# Battery_and_Power.net
KiCad netlist of a schematic drawn in Altium Designer
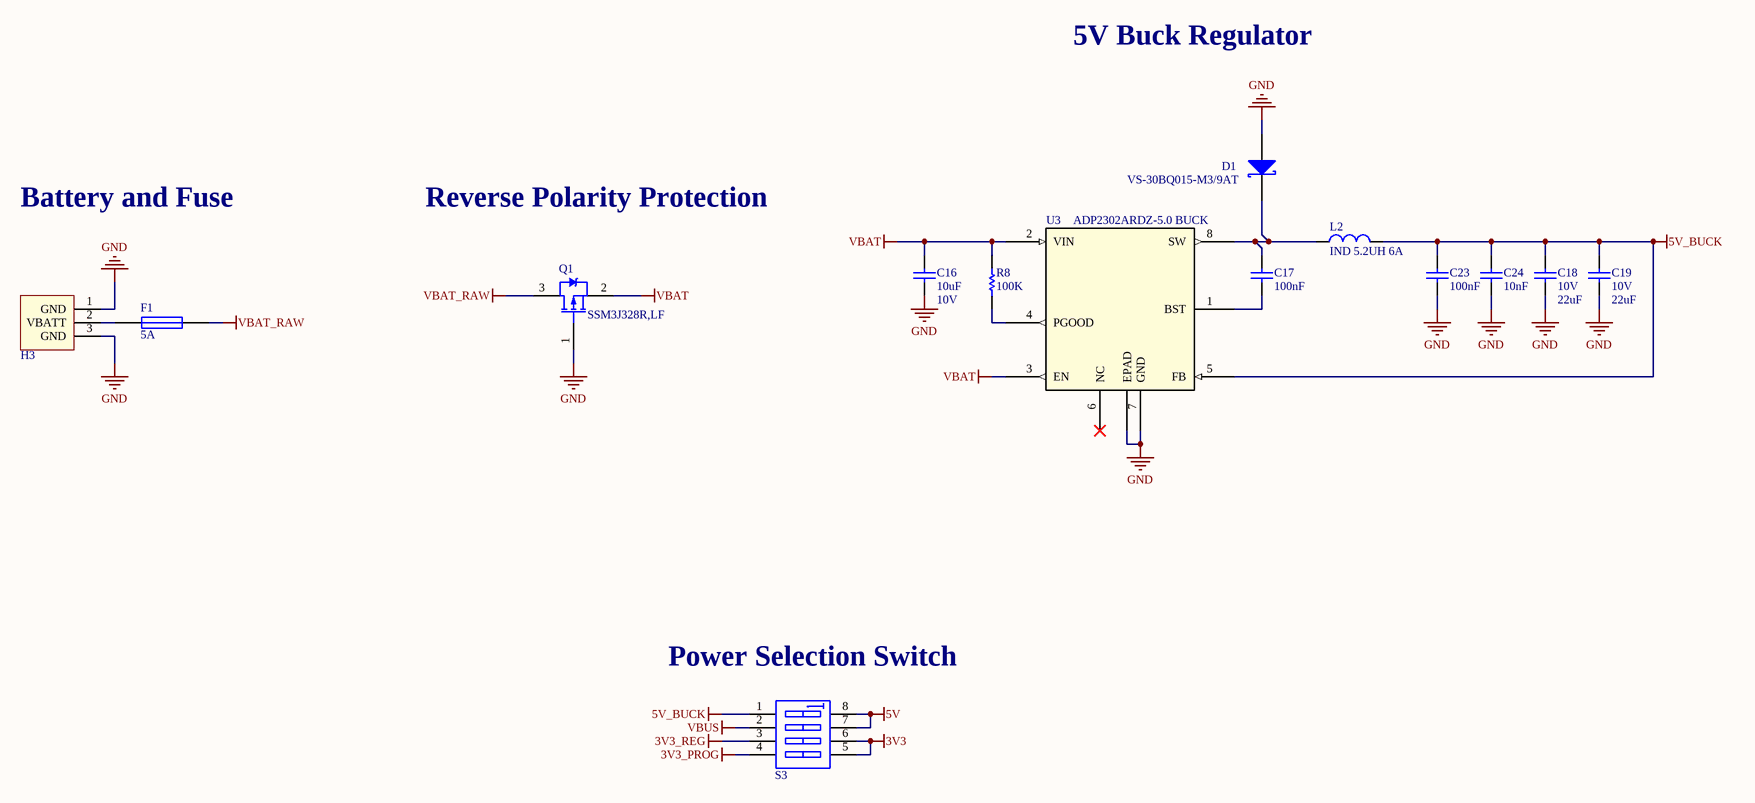
[diagram p0: Battery and Power.SchDoc]

(export (version "E")
  (design (tool "Eeschema 10.0.6"))
  (components
    (comp (ref "C16")
      (value "10uF")
      (footprint "CAPC2012L")
      (description "CAP CER 10uF X7R +-20% 10V 0805")
      (fields (field (name "MAX VOLTAGE") "10V"))
      (libsource (lib "ECE AD19Components_19V1") (part "CC_10uF_0805_10V"))
    )
    (comp (ref "C17")
      (value "100nF")
      (footprint "CAPC1608L")
      (description "CAP CER 100nF X7R +-10% 50V 0603")
      (libsource (lib "ECE AD19Components_19V1") (part "CC_100nF_0603"))
    )
    (comp (ref "C18")
      (value "22uF")
      (footprint "CAPC3216L")
      (description "CAP CER 22uF Y5V -20% +80% 10V 1206")
      (fields (field (name "MAX VOLTAGE") "10V"))
      (libsource (lib "ECE AD19Components_19V1") (part "CC_22uF_1206"))
    )
    (comp (ref "C19")
      (value "22uF")
      (footprint "CAPC3216L")
      (description "CAP CER 22uF Y5V -20% +80% 10V 1206")
      (fields (field (name "MAX VOLTAGE") "10V"))
      (libsource (lib "ECE AD19Components_19V1") (part "CC_22uF_1206"))
    )
    (comp (ref "C23")
      (value "100nF")
      (footprint "CAPC1608L")
      (description "CAP CER 100nF X7R +-10% 50V 0603")
      (libsource (lib "ECE AD19Components_19V1") (part "CC_100nF_0603"))
    )
    (comp (ref "C24")
      (value "10nF")
      (footprint "CAPC1608L")
      (description "CAP CER 10nF X7R +-10% 50V 0603")
      (libsource (lib "ECE AD19Components_19V1") (part "CC_10nF_0603"))
    )
    (comp (ref "D1")
      (value "VS-30BQ015-M3/9AT")
      (footprint "SMC")
      (description "DIODE, SCHOTTKY, 3A, 15V, DO-214AB / SMC")
      (fields (field (name "MANUFACTURER") "Vishay Semiconductors"))
      (libsource (lib "ECE AD19Components_19V1") (part "DS_VS-30BQ015-M3"))
    )
    (comp (ref "F1")
      (value "5A")
      (footprint "RESC3216N")
      (description "Fuse 5.0A Fast Acting 1206 SMD")
      (fields (field (name "MANUFACTURER PART NUMBER") "C1F5") (field (name "MANUFACTURER") "Bel TRP"))
      (libsource (lib "ECE AD19Components_19V1") (part "FS_Fuse_5.0A"))
    )
    (comp (ref "H3")
      (value "Battery_HEADER_3pin")
      (footprint "BATT_HEADER_3POS")
      (description "3Pin Header 2.54mm spacing")
      (libsource (lib "ENCE461AD19_19V2") (part "Battery_HEADER_3pin"))
    )
    (comp (ref "L2")
      (value "IND 5.2UH 6A")
      (footprint "INDUCTOR5u2")
      (description "FIXED IND 5.2UH 6A 22 MOHM SMD")
      (fields
        (field (name "MANUFACTURER") "Sumida America Components Inc.")
        (field (name "MANUFACTURER PART NUMBER") "CDRH104RNP-5R2NC")
      )
      (libsource (lib "ENCE461AD19_19V2") (part "CDRH104RNP-5R2NC"))
    )
    (comp (ref "Q1")
      (value "SSM3J328R,LF")
      (footprint "SOT23_L")
      (description "MOSFET P-CH 20V 6A SOT23-3")
      (fields
        (field (name "MANUFACTURER") "Toshiba")
        (field (name "MANUFACTURER PART NUMBER") "SSM3J328R,LF")
      )
      (libsource (lib "ECE AD19Components_19V1") (part "TM_SSM3J328R"))
    )
    (comp (ref "R8")
      (value "100K")
      (footprint "RESC1608L")
      (description "RES 100K OHM 1/10W 5% 0603 SMD")
      (libsource (lib "ECE AD19Components_19V1") (part "RS_100K"))
    )
    (comp (ref "S3")
      (value "WS_SW DIP-4")
      (footprint "DIP_SW_4WAY_SMD -")
      (description "DIP Switch, 4 Position, SPST SMD")
      (fields
        (field (name "MANUFACTURER") "OMRON ELECTRONIC COMPONENTS")
        (field (name "MANUFACTURER PART NUMBER") "A6SN-4101")
      )
      (libsource (lib "ECE AD19Components_19V1") (part "WS_SW DIP-4"))
    )
    (comp (ref "U3")
      (value "ADP2302ARDZ-5.0 BUCK")
      (footprint "RD_8_1")
      (description "IC REG BUCK 5V 2A 8SOIC")
      (fields (field (name "MANUFACTURER_PART_NUMBER") "ADP2302ARDZ-5.0-R7"))
      (libsource (lib "ENCE461AD19_19V2") (part "ADP2302ARDZ-5.0-R7"))
    )
  )
  (nets
    (net (code "1") (name "3V3") (class "Default")
      (node (ref "S3") (pin "5") (pinfunction "B4_5") (pintype "passive"))
      (node (ref "S3") (pin "6") (pinfunction "B3_6") (pintype "passive"))
    )
    (net (code "2") (name "3V3_PROG") (class "Default")
      (node (ref "S3") (pin "4") (pinfunction "A4_4") (pintype "passive"))
    )
    (net (code "3") (name "3V3_REG") (class "Default")
      (node (ref "S3") (pin "3") (pinfunction "A3_3") (pintype "passive"))
    )
    (net (code "4") (name "5V") (class "Default")
      (node (ref "S3") (pin "7") (pinfunction "B2_7") (pintype "passive"))
      (node (ref "S3") (pin "8") (pinfunction "B1_8") (pintype "passive"))
    )
    (net (code "5") (name "5V_BUCK") (class "Default")
      (node (ref "C18") (pin "2") (pinfunction "2_2") (pintype "passive"))
      (node (ref "C19") (pin "2") (pinfunction "2_2") (pintype "passive"))
      (node (ref "C23") (pin "2") (pinfunction "2_2") (pintype "passive"))
      (node (ref "C24") (pin "2") (pinfunction "2_2") (pintype "passive"))
      (node (ref "L2") (pin "2") (pintype "passive"))
      (node (ref "S3") (pin "1") (pinfunction "A1_1") (pintype "passive"))
      (node (ref "U3") (pin "5") (pinfunction "FB_5") (pintype "input"))
    )
    (net (code "6") (name "GND") (class "Default")
      (node (ref "C16") (pin "1") (pinfunction "1_1") (pintype "passive"))
      (node (ref "C18") (pin "1") (pinfunction "1_1") (pintype "passive"))
      (node (ref "C19") (pin "1") (pinfunction "1_1") (pintype "passive"))
      (node (ref "C23") (pin "1") (pinfunction "1_1") (pintype "passive"))
      (node (ref "C24") (pin "1") (pinfunction "1_1") (pintype "passive"))
      (node (ref "D1") (pin "1") (pinfunction "A_1") (pintype "passive"))
      (node (ref "H3") (pin "1") (pinfunction "GND_1") (pintype "passive"))
      (node (ref "H3") (pin "3") (pinfunction "GND_3") (pintype "passive"))
      (node (ref "Q1") (pin "1") (pinfunction "1_1") (pintype "passive"))
      (node (ref "U3") (pin "7") (pinfunction "GND_7") (pintype "power_in"))
      (node (ref "U3") (pin "EPAD") (pinfunction "EPAD_EPAD") (pintype "passive"))
    )
    (net (code "7") (name "Net-(D1-K)") (class "Default")
      (node (ref "C17") (pin "2") (pinfunction "2_2") (pintype "passive"))
      (node (ref "D1") (pin "2") (pinfunction "K_2") (pintype "passive"))
      (node (ref "L2") (pin "1") (pintype "passive"))
      (node (ref "U3") (pin "8") (pinfunction "SW_8") (pintype "output"))
    )
    (net (code "8") (name "Net-(H3-VBATT)") (class "Default")
      (node (ref "F1") (pin "1") (pinfunction "1_1") (pintype "passive"))
      (node (ref "H3") (pin "2") (pinfunction "VBATT_2") (pintype "passive"))
    )
    (net (code "9") (name "Net-(U3-BST)") (class "Default")
      (node (ref "C17") (pin "1") (pinfunction "1_1") (pintype "passive"))
      (node (ref "U3") (pin "1") (pinfunction "BST_1") (pintype "passive"))
    )
    (net (code "10") (name "Net-(U3-PGOOD)") (class "Default")
      (node (ref "R8") (pin "1") (pinfunction "1_1") (pintype "passive"))
      (node (ref "U3") (pin "4") (pinfunction "PGOOD_4") (pintype "output"))
    )
    (net (code "11") (name "VBAT") (class "Default")
      (node (ref "C16") (pin "2") (pinfunction "2_2") (pintype "passive"))
      (node (ref "Q1") (pin "2") (pinfunction "2_2") (pintype "passive"))
      (node (ref "R8") (pin "2") (pinfunction "2_2") (pintype "passive"))
      (node (ref "U3") (pin "2") (pinfunction "VIN_2") (pintype "input"))
      (node (ref "U3") (pin "3") (pinfunction "EN_3") (pintype "output"))
    )
    (net (code "12") (name "VBAT_RAW") (class "Default")
      (node (ref "F1") (pin "2") (pinfunction "2_2") (pintype "passive"))
      (node (ref "Q1") (pin "3") (pinfunction "3_3") (pintype "passive"))
    )
    (net (code "13") (name "VBUS") (class "Default")
      (node (ref "S3") (pin "2") (pinfunction "A2_2") (pintype "passive"))
    )
    (net (code "14") (name "unconnected-(U3-NC-Pad6)") (class "Default")
      (node (ref "U3") (pin "6") (pinfunction "NC_6") (pintype "passive+no_connect"))
    )
  )
)
